# Control_Board.net
KiCad netlist of a schematic drawn in EAGLE
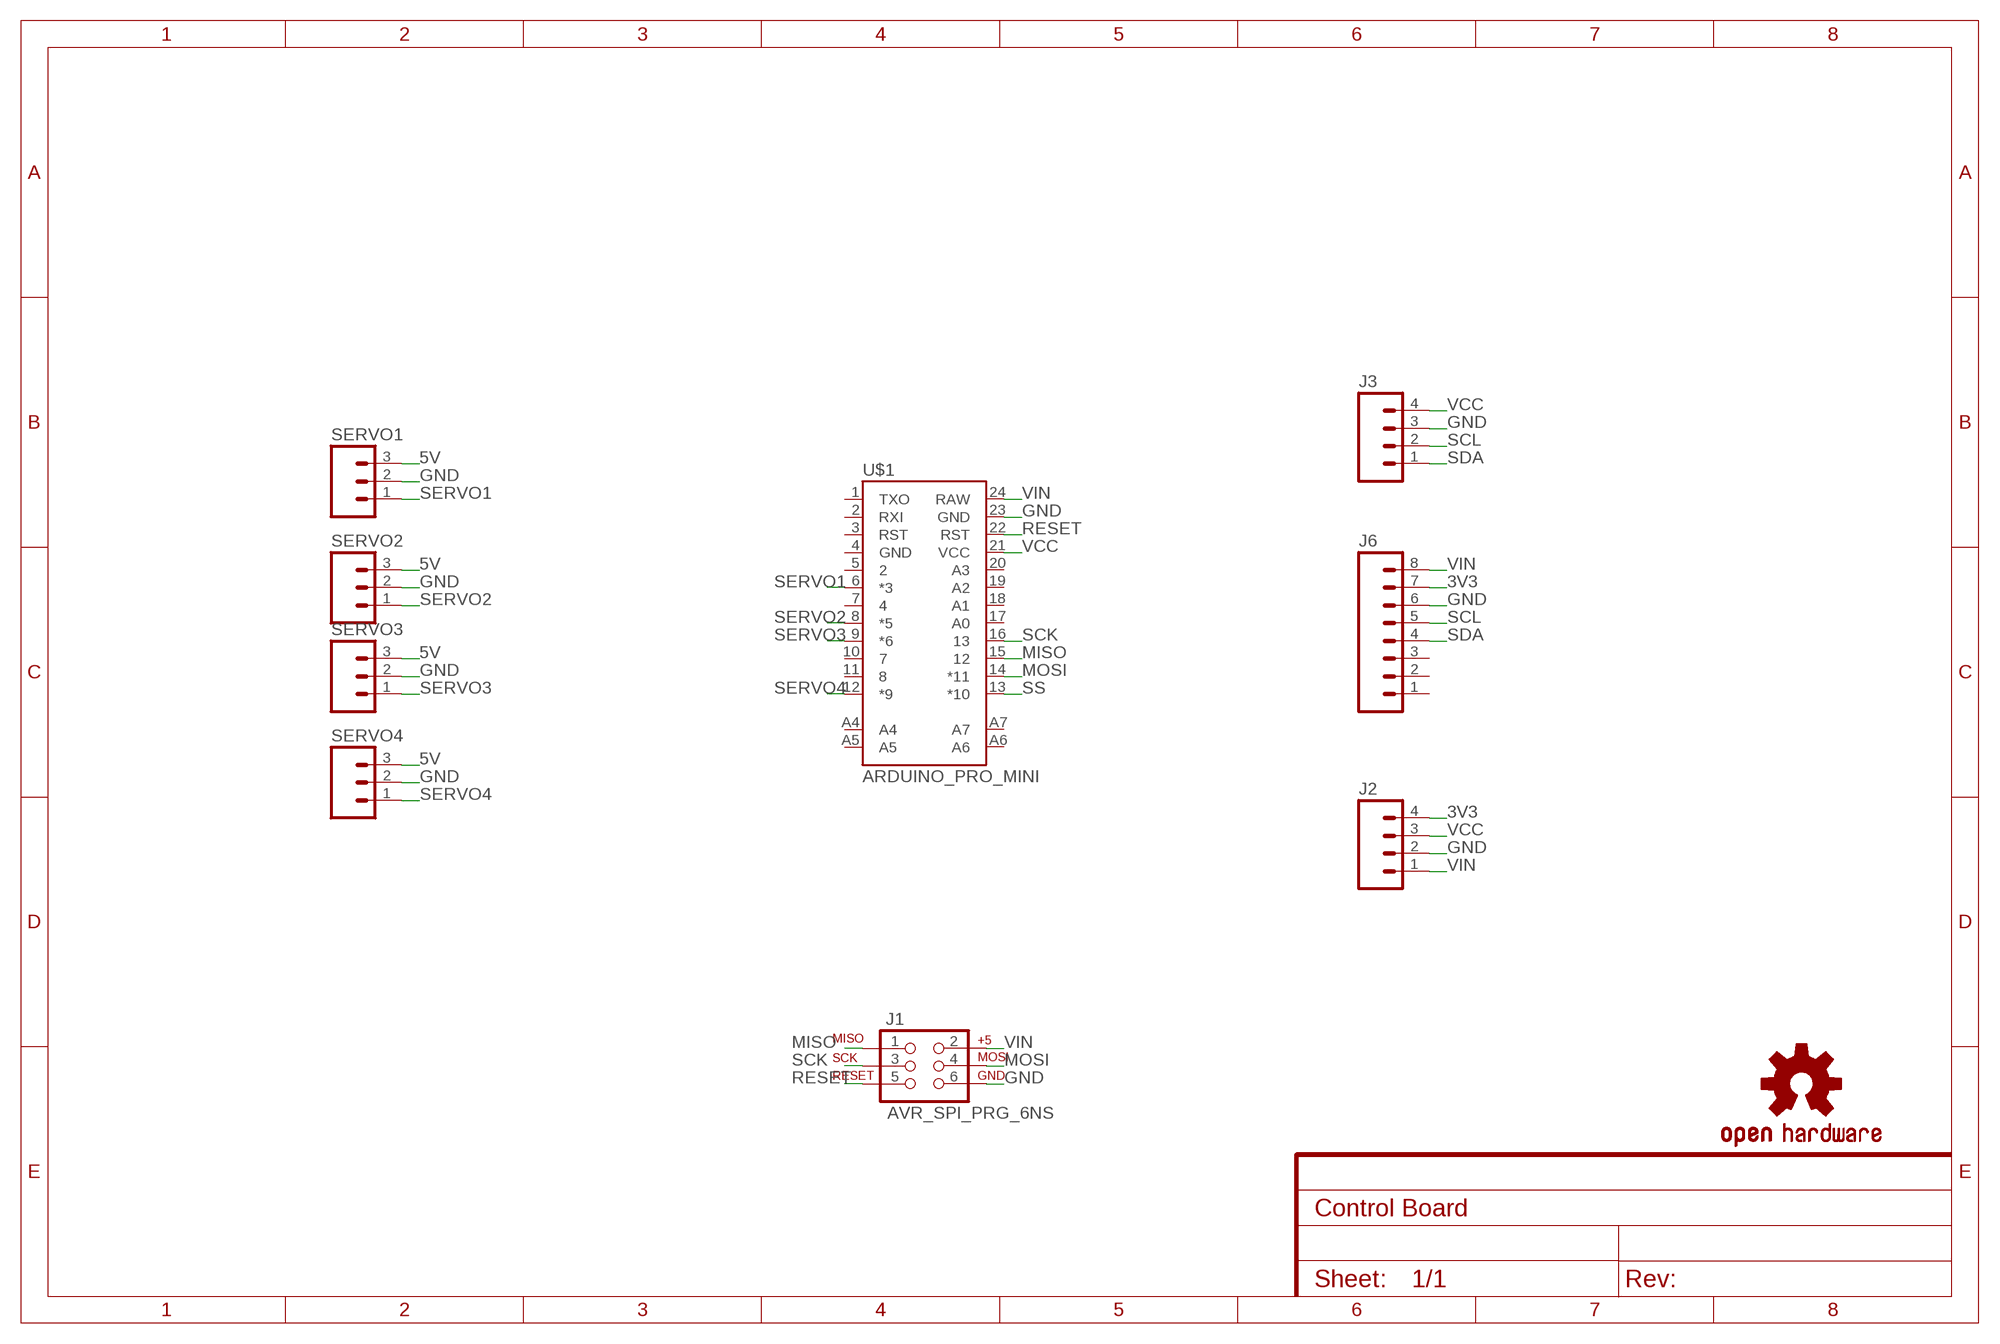
[diagram p0: schematic, sheet 1]

(export (version "E")
  (design (tool "Eeschema 10.0.6"))
  (components
    (comp (ref "J1")
      (value "AVR_SPI_PRG_6NS")
      (footprint "eagle-import:2X3-NS")
      (libsource (lib "eagle-import") (part "AVR_SPI_PRG_6NS"))
    )
    (comp (ref "J2")
      (value "M04PTH")
      (footprint "eagle-import:1X04")
      (libsource (lib "eagle-import") (part "M04PTH"))
    )
    (comp (ref "J3")
      (value "M04PTH")
      (footprint "eagle-import:1X04")
      (libsource (lib "eagle-import") (part "M04PTH"))
    )
    (comp (ref "J6")
      (value "M08")
      (footprint "eagle-import:1X08_ROUND")
      (libsource (lib "eagle-import") (part "M08"))
    )
    (comp (ref "LOGO1")
      (value "OSHW-LOGOM-COPPER")
      (footprint "eagle-import:OSHW-LOGO-M_COPPER")
      (libsource (lib "eagle-import") (part "OSHW-LOGOM-COPPER"))
    )
    (comp (ref "SERVO1")
      (value "M03PTH")
      (footprint "eagle-import:1X03")
      (libsource (lib "eagle-import") (part "M03PTH"))
    )
    (comp (ref "SERVO2")
      (value "M03PTH")
      (footprint "eagle-import:1X03")
      (libsource (lib "eagle-import") (part "M03PTH"))
    )
    (comp (ref "SERVO3")
      (value "M03PTH")
      (footprint "eagle-import:1X03")
      (libsource (lib "eagle-import") (part "M03PTH"))
    )
    (comp (ref "SERVO4")
      (value "M03PTH")
      (footprint "eagle-import:1X03")
      (libsource (lib "eagle-import") (part "M03PTH"))
    )
    (comp (ref "U$1")
      (value "ARDUINO_PRO_MINI")
      (footprint "eagle-import:ARDUINO_PRO_MINI")
      (libsource (lib "eagle-import") (part "ARDUINO_PRO_MINI"))
    )
  )
  (nets
    (net (code "1") (name "/3V3") (class "Default")
      (node (ref "J2") (pin "4") (pinfunction "4_4") (pintype "passive"))
      (node (ref "J6") (pin "7") (pinfunction "7_7") (pintype "passive"))
    )
    (net (code "2") (name "/5V") (class "Default")
      (node (ref "SERVO1") (pin "3") (pinfunction "3_3") (pintype "passive"))
      (node (ref "SERVO2") (pin "3") (pinfunction "3_3") (pintype "passive"))
      (node (ref "SERVO3") (pin "3") (pinfunction "3_3") (pintype "passive"))
      (node (ref "SERVO4") (pin "3") (pinfunction "3_3") (pintype "passive"))
    )
    (net (code "3") (name "/GND") (class "Default")
      (node (ref "J1") (pin "6") (pinfunction "6_6") (pintype "passive"))
      (node (ref "J2") (pin "2") (pinfunction "2_2") (pintype "passive"))
      (node (ref "J3") (pin "3") (pinfunction "3_3") (pintype "passive"))
      (node (ref "J6") (pin "6") (pinfunction "6_6") (pintype "passive"))
      (node (ref "SERVO1") (pin "2") (pinfunction "2_2") (pintype "passive"))
      (node (ref "SERVO2") (pin "2") (pinfunction "2_2") (pintype "passive"))
      (node (ref "SERVO3") (pin "2") (pinfunction "2_2") (pintype "passive"))
      (node (ref "SERVO4") (pin "2") (pinfunction "2_2") (pintype "passive"))
      (node (ref "U$1") (pin "23") (pinfunction "GND_23") (pintype "bidirectional"))
    )
    (net (code "4") (name "/MISO") (class "Default")
      (node (ref "J1") (pin "1") (pinfunction "1_1") (pintype "passive"))
      (node (ref "U$1") (pin "15") (pinfunction "12_15") (pintype "bidirectional"))
    )
    (net (code "5") (name "/MOSI") (class "Default")
      (node (ref "J1") (pin "4") (pinfunction "4_4") (pintype "passive"))
      (node (ref "U$1") (pin "14") (pinfunction "*11_14") (pintype "bidirectional"))
    )
    (net (code "6") (name "/RESET") (class "Default")
      (node (ref "J1") (pin "5") (pinfunction "5_5") (pintype "passive"))
      (node (ref "U$1") (pin "22") (pinfunction "RST_22") (pintype "bidirectional"))
    )
    (net (code "7") (name "/SCK") (class "Default")
      (node (ref "J1") (pin "3") (pinfunction "3_3") (pintype "passive"))
      (node (ref "U$1") (pin "16") (pinfunction "13_16") (pintype "bidirectional"))
    )
    (net (code "8") (name "/SCL") (class "Default")
      (node (ref "J3") (pin "2") (pinfunction "2_2") (pintype "passive"))
      (node (ref "J6") (pin "5") (pinfunction "5_5") (pintype "passive"))
    )
    (net (code "9") (name "/SDA") (class "Default")
      (node (ref "J3") (pin "1") (pinfunction "1_1") (pintype "passive"))
      (node (ref "J6") (pin "4") (pinfunction "4_4") (pintype "passive"))
    )
    (net (code "10") (name "/SERVO1") (class "Default")
      (node (ref "SERVO1") (pin "1") (pinfunction "1_1") (pintype "passive"))
      (node (ref "U$1") (pin "6") (pinfunction "*3_6") (pintype "bidirectional"))
    )
    (net (code "11") (name "/SERVO2") (class "Default")
      (node (ref "SERVO2") (pin "1") (pinfunction "1_1") (pintype "passive"))
      (node (ref "U$1") (pin "8") (pinfunction "*5_8") (pintype "bidirectional"))
    )
    (net (code "12") (name "/SERVO3") (class "Default")
      (node (ref "SERVO3") (pin "1") (pinfunction "1_1") (pintype "passive"))
      (node (ref "U$1") (pin "9") (pinfunction "*6_9") (pintype "bidirectional"))
    )
    (net (code "13") (name "/SERVO4") (class "Default")
      (node (ref "SERVO4") (pin "1") (pinfunction "1_1") (pintype "passive"))
      (node (ref "U$1") (pin "12") (pinfunction "*9_12") (pintype "bidirectional"))
    )
    (net (code "14") (name "/SS") (class "Default")
      (node (ref "U$1") (pin "13") (pinfunction "*10_13") (pintype "bidirectional"))
    )
    (net (code "15") (name "/VCC") (class "Default")
      (node (ref "J2") (pin "3") (pinfunction "3_3") (pintype "passive"))
      (node (ref "J3") (pin "4") (pinfunction "4_4") (pintype "passive"))
      (node (ref "U$1") (pin "21") (pinfunction "VCC_21") (pintype "bidirectional"))
    )
    (net (code "16") (name "/VIN") (class "Default")
      (node (ref "J1") (pin "2") (pinfunction "2_2") (pintype "passive"))
      (node (ref "J2") (pin "1") (pinfunction "1_1") (pintype "passive"))
      (node (ref "J6") (pin "8") (pinfunction "8_8") (pintype "passive"))
      (node (ref "U$1") (pin "24") (pinfunction "RAW_24") (pintype "bidirectional"))
    )
    (net (code "17") (name "unconnected-(J6-Pad1)") (class "Default")
      (node (ref "J6") (pin "1") (pinfunction "1_1") (pintype "passive"))
    )
    (net (code "18") (name "unconnected-(J6-Pad2)") (class "Default")
      (node (ref "J6") (pin "2") (pinfunction "2_2") (pintype "passive"))
    )
    (net (code "19") (name "unconnected-(J6-Pad3)") (class "Default")
      (node (ref "J6") (pin "3") (pinfunction "3_3") (pintype "passive"))
    )
    (net (code "20") (name "unconnected-(U$1-2-Pad5)") (class "Default")
      (node (ref "U$1") (pin "5") (pinfunction "2_5") (pintype "bidirectional"))
    )
    (net (code "21") (name "unconnected-(U$1-4-Pad7)") (class "Default")
      (node (ref "U$1") (pin "7") (pinfunction "4_7") (pintype "bidirectional"))
    )
    (net (code "22") (name "unconnected-(U$1-7-Pad10)") (class "Default")
      (node (ref "U$1") (pin "10") (pinfunction "7_10") (pintype "bidirectional"))
    )
    (net (code "23") (name "unconnected-(U$1-8-Pad11)") (class "Default")
      (node (ref "U$1") (pin "11") (pinfunction "8_11") (pintype "bidirectional"))
    )
    (net (code "24") (name "unconnected-(U$1-A0-Pad17)") (class "Default")
      (node (ref "U$1") (pin "17") (pinfunction "A0_17") (pintype "bidirectional"))
    )
    (net (code "25") (name "unconnected-(U$1-A1-Pad18)") (class "Default")
      (node (ref "U$1") (pin "18") (pinfunction "A1_18") (pintype "bidirectional"))
    )
    (net (code "26") (name "unconnected-(U$1-A2-Pad19)") (class "Default")
      (node (ref "U$1") (pin "19") (pinfunction "A2_19") (pintype "bidirectional"))
    )
    (net (code "27") (name "unconnected-(U$1-A3-Pad20)") (class "Default")
      (node (ref "U$1") (pin "20") (pinfunction "A3_20") (pintype "bidirectional"))
    )
    (net (code "28") (name "unconnected-(U$1-GND-Pad4)") (class "Default")
      (node (ref "U$1") (pin "4") (pinfunction "GND_4") (pintype "bidirectional"))
    )
    (net (code "29") (name "unconnected-(U$1-PadA4)") (class "Default")
      (node (ref "U$1") (pin "A4") (pinfunction "A4_A4") (pintype "bidirectional"))
    )
    (net (code "30") (name "unconnected-(U$1-PadA5)") (class "Default")
      (node (ref "U$1") (pin "A5") (pinfunction "A5_A5") (pintype "bidirectional"))
    )
    (net (code "31") (name "unconnected-(U$1-PadA6)") (class "Default")
      (node (ref "U$1") (pin "A6") (pinfunction "A6_A6") (pintype "bidirectional"))
    )
    (net (code "32") (name "unconnected-(U$1-PadA7)") (class "Default")
      (node (ref "U$1") (pin "A7") (pinfunction "A7_A7") (pintype "bidirectional"))
    )
    (net (code "33") (name "unconnected-(U$1-RST-Pad3)") (class "Default")
      (node (ref "U$1") (pin "3") (pinfunction "RST_3") (pintype "bidirectional"))
    )
    (net (code "34") (name "unconnected-(U$1-RXI-Pad2)") (class "Default")
      (node (ref "U$1") (pin "2") (pinfunction "RXI_2") (pintype "bidirectional"))
    )
    (net (code "35") (name "unconnected-(U$1-TXO-Pad1)") (class "Default")
      (node (ref "U$1") (pin "1") (pinfunction "TXO_1") (pintype "bidirectional"))
    )
  )
)
